# ESP32-USBC.net
KiCad netlist of a schematic drawn in Altium Designer
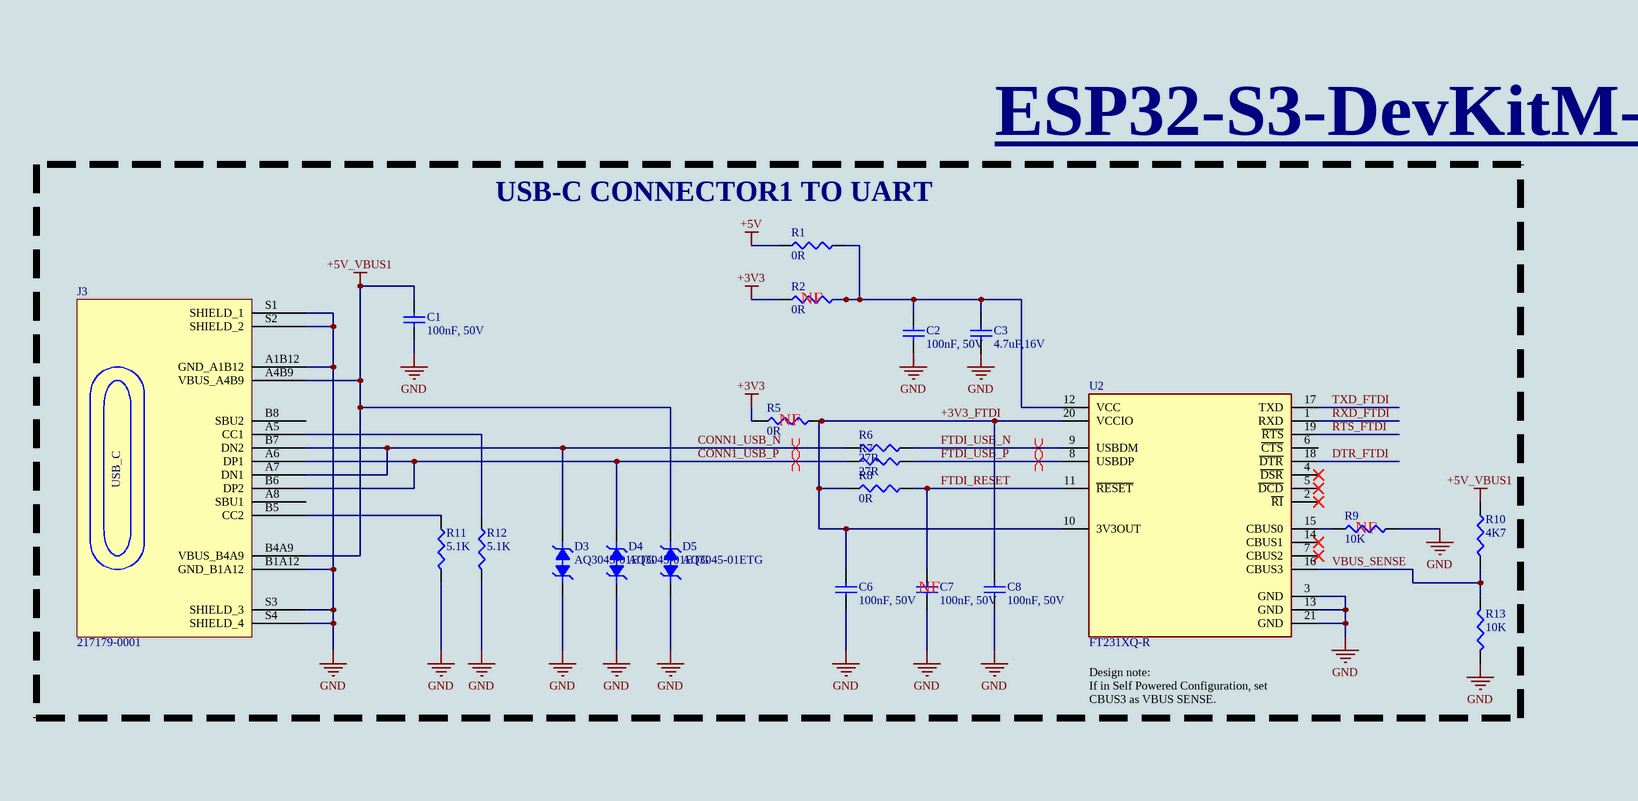
[diagram p0: ESP32-USBC.SchDoc, top left]
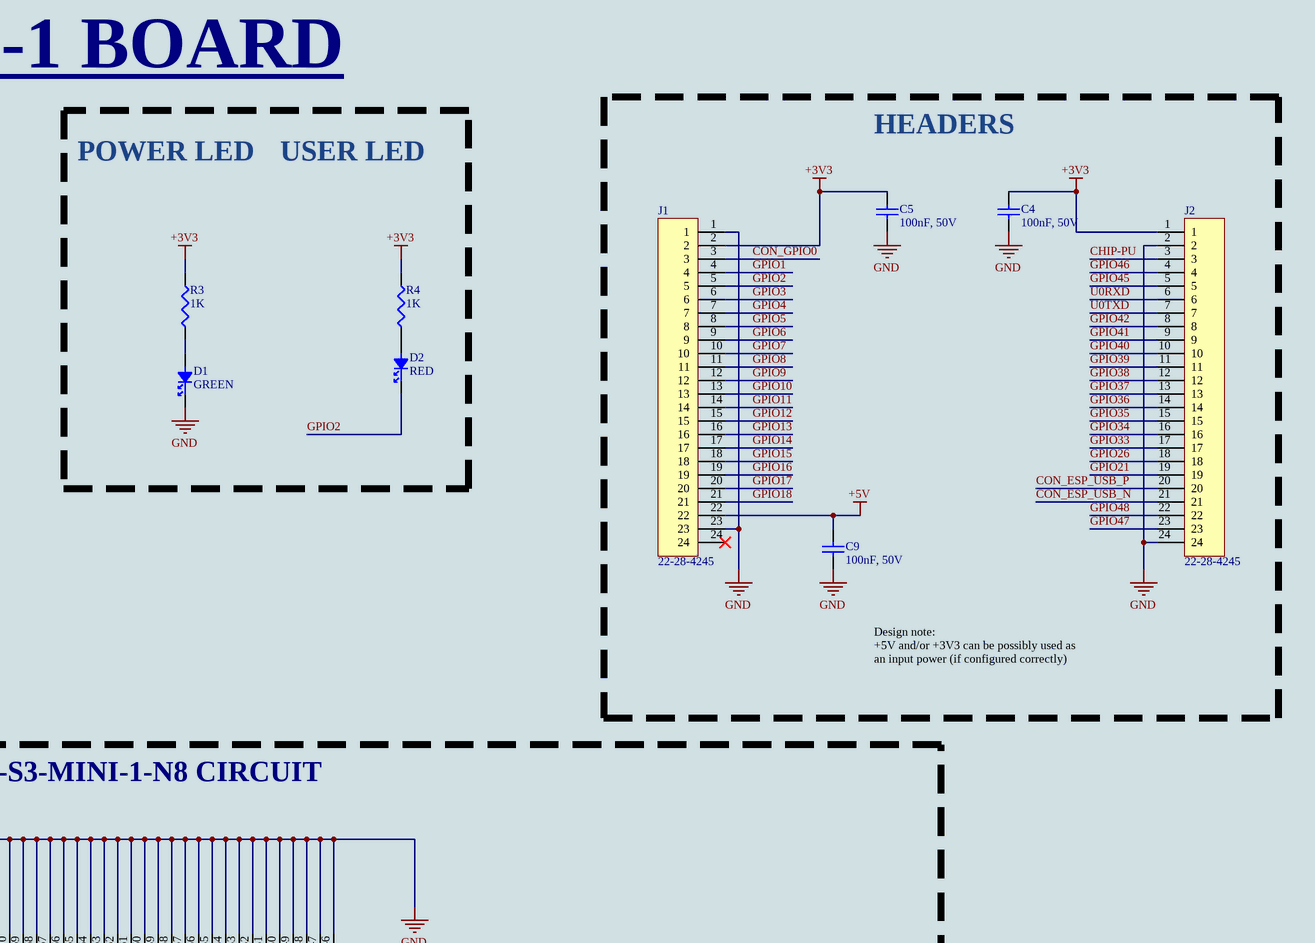
[diagram p1: ESP32-USBC.SchDoc, top right]
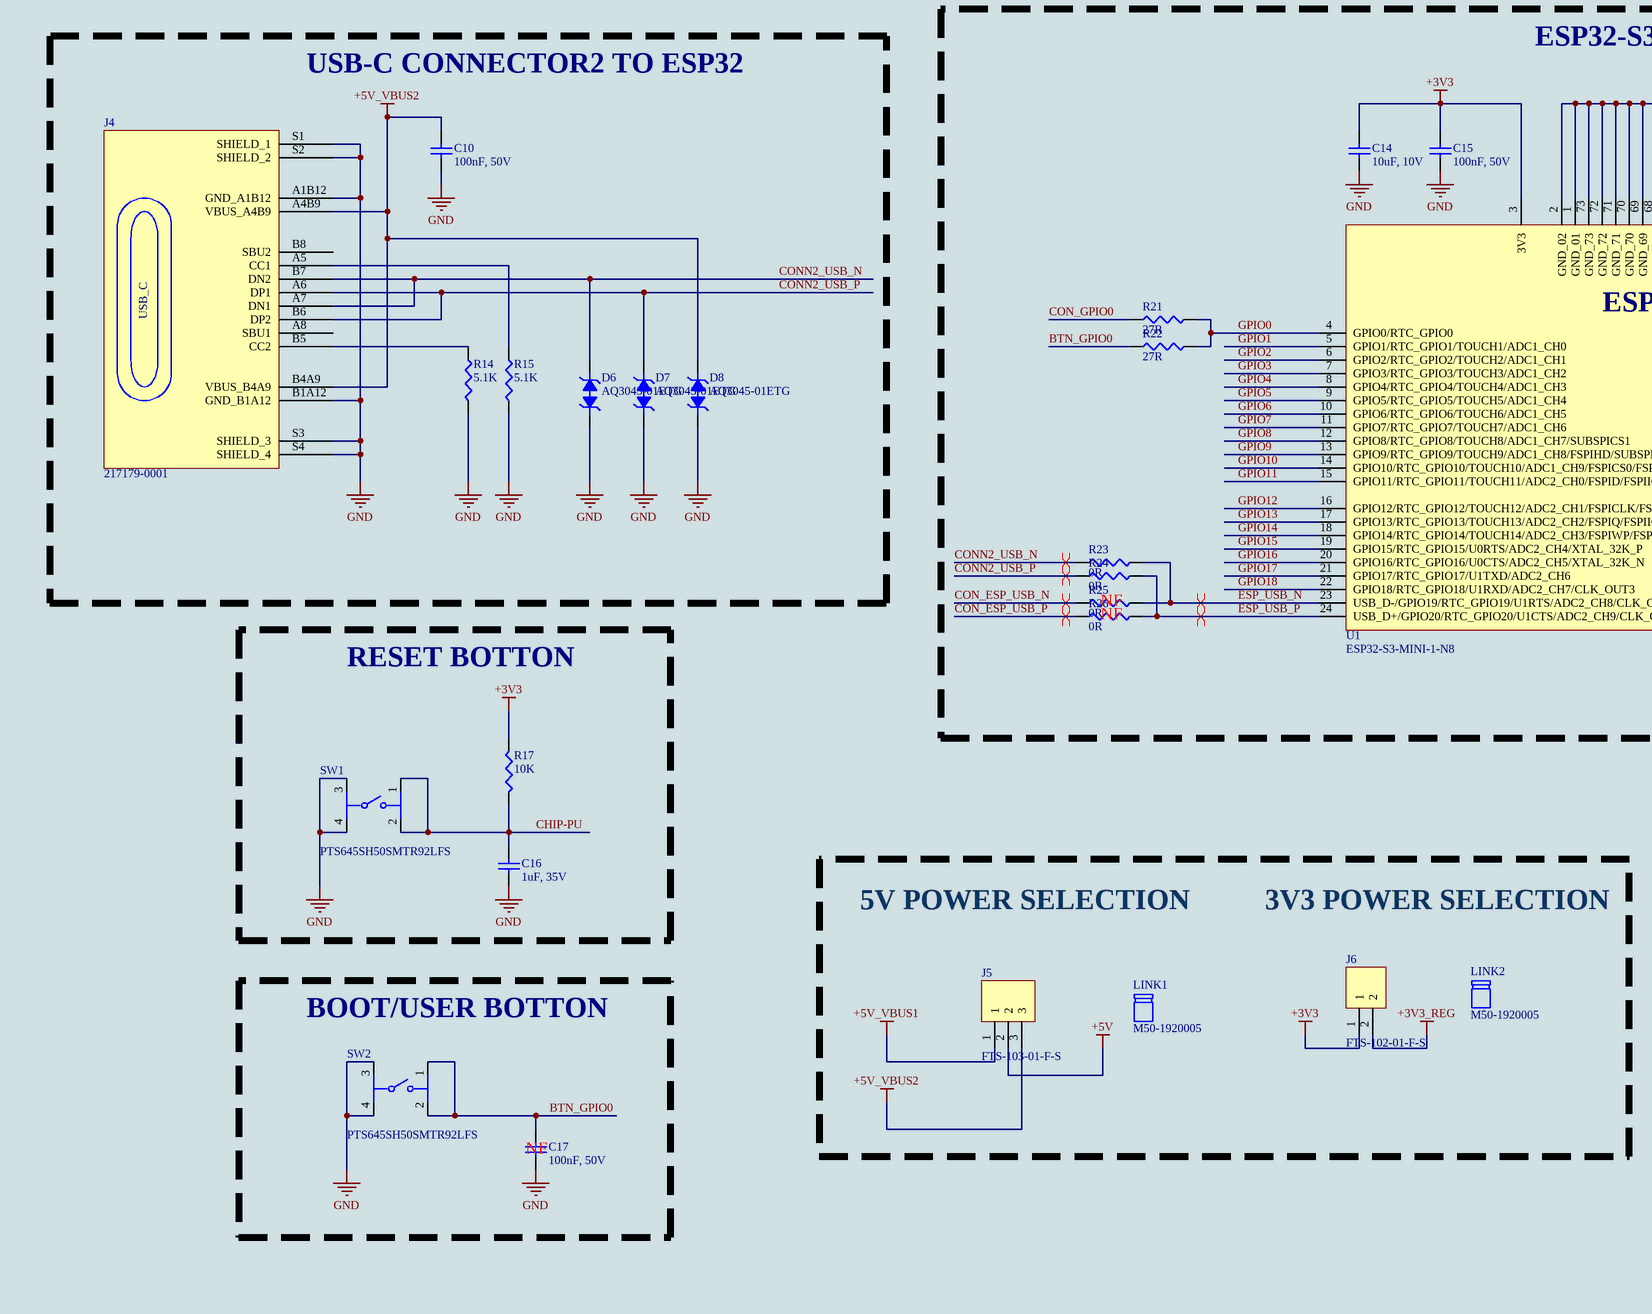
[diagram p2: ESP32-USBC.SchDoc, bottom left]
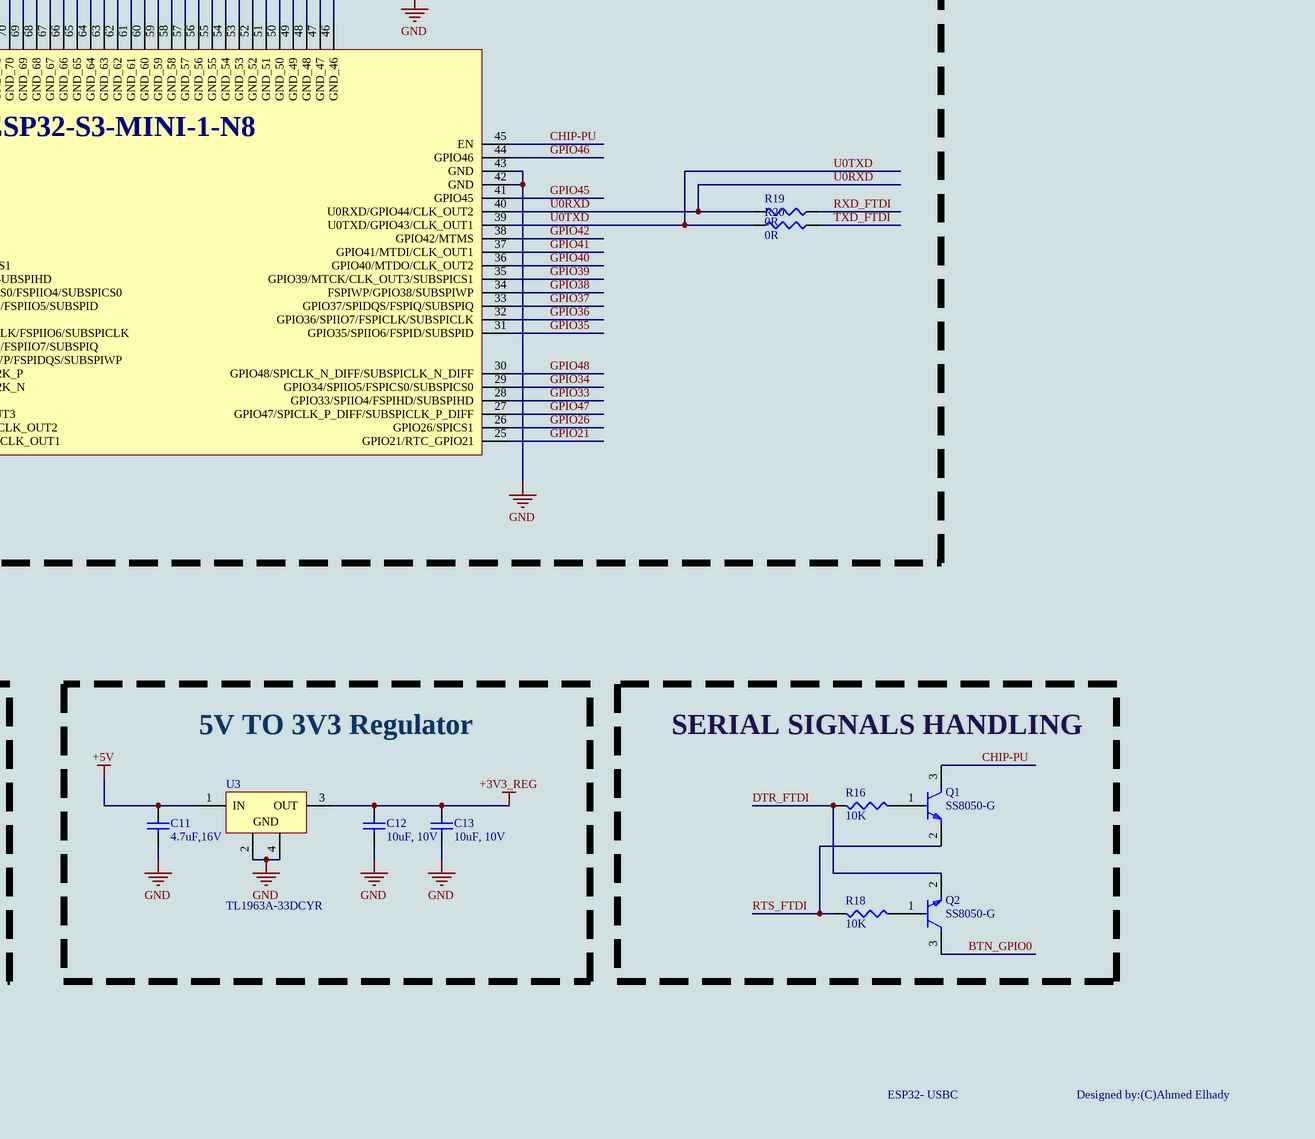
[diagram p3: ESP32-USBC.SchDoc, bottom right]

(export (version "E")
  (design (tool "Eeschema 10.0.6"))
  (components
    (comp (ref "C1")
      (value "100nF, 50V")
      (footprint "CAPC1005X90N")
      (description "50V 100nF X7R ±10% 0402 Multilayer Ceramic Capacitors MLCC - SMD/SMT ROHS")
      (fields
        (field (name "MANUFACTURER") "Samsung Electro-Mechanics")
        (field (name "MANUFACTURER PART NUMBER") "CL05B104KB54PNC")
      )
      (libsource (lib "Schlib") (part "CL05B104KB54PNC"))
    )
    (comp (ref "C2")
      (value "100nF, 50V")
      (footprint "CAPC1005X90N")
      (description "50V 100nF X7R ±10% 0402 Multilayer Ceramic Capacitors MLCC - SMD/SMT ROHS")
      (fields
        (field (name "MANUFACTURER") "Samsung Electro-Mechanics")
        (field (name "MANUFACTURER PART NUMBER") "CL05B104KB54PNC")
      )
      (libsource (lib "Schlib") (part "CL05B104KB54PNC"))
    )
    (comp (ref "C3")
      (value "4.7uF,16V")
      (footprint "CAPC1005X90N")
      (description "4.7 µF ±20% 16V Ceramic Capacitor X5R 0402 (1005 Metric)")
      (fields
        (field (name "MANUFACTURER") "Samsung Electro-Mechanics")
        (field (name "MANUFACTURER PART NUMBER") "CL05A475MO5NUNC")
      )
      (libsource (lib "Schlib") (part "CL05A475MO5NUNC"))
    )
    (comp (ref "C4")
      (value "100nF, 50V")
      (footprint "CAPC1005X90N")
      (description "50V 100nF X7R ±10% 0402 Multilayer Ceramic Capacitors MLCC - SMD/SMT ROHS")
      (fields
        (field (name "MANUFACTURER") "Samsung Electro-Mechanics")
        (field (name "MANUFACTURER PART NUMBER") "CL05B104KB54PNC")
      )
      (libsource (lib "Schlib") (part "CL05B104KB54PNC"))
    )
    (comp (ref "C5")
      (value "100nF, 50V")
      (footprint "CAPC1005X90N")
      (description "50V 100nF X7R ±10% 0402 Multilayer Ceramic Capacitors MLCC - SMD/SMT ROHS")
      (fields
        (field (name "MANUFACTURER") "Samsung Electro-Mechanics")
        (field (name "MANUFACTURER PART NUMBER") "CL05B104KB54PNC")
      )
      (libsource (lib "Schlib") (part "CL05B104KB54PNC"))
    )
    (comp (ref "C6")
      (value "100nF, 50V")
      (footprint "CAPC1005X90N")
      (description "50V 100nF X7R ±10% 0402 Multilayer Ceramic Capacitors MLCC - SMD/SMT ROHS")
      (fields
        (field (name "MANUFACTURER") "Samsung Electro-Mechanics")
        (field (name "MANUFACTURER PART NUMBER") "CL05B104KB54PNC")
      )
      (libsource (lib "Schlib") (part "CL05B104KB54PNC"))
    )
    (comp (ref "C7")
      (value "100nF, 50V")
      (footprint "CAPC1005X90N")
      (description "50V 100nF X7R ±10% 0402 Multilayer Ceramic Capacitors MLCC - SMD/SMT ROHS")
      (fields
        (field (name "MANUFACTURER") "Samsung Electro-Mechanics")
        (field (name "MANUFACTURER PART NUMBER") "CL05B104KB54PNC")
      )
      (libsource (lib "Schlib") (part "CL05B104KB54PNC"))
    )
    (comp (ref "C8")
      (value "100nF, 50V")
      (footprint "CAPC1005X90N")
      (description "50V 100nF X7R ±10% 0402 Multilayer Ceramic Capacitors MLCC - SMD/SMT ROHS")
      (fields
        (field (name "MANUFACTURER") "Samsung Electro-Mechanics")
        (field (name "MANUFACTURER PART NUMBER") "CL05B104KB54PNC")
      )
      (libsource (lib "Schlib") (part "CL05B104KB54PNC"))
    )
    (comp (ref "C9")
      (value "100nF, 50V")
      (footprint "CAPC1005X90N")
      (description "50V 100nF X7R ±10% 0402 Multilayer Ceramic Capacitors MLCC - SMD/SMT ROHS")
      (fields
        (field (name "MANUFACTURER") "Samsung Electro-Mechanics")
        (field (name "MANUFACTURER PART NUMBER") "CL05B104KB54PNC")
      )
      (libsource (lib "Schlib") (part "CL05B104KB54PNC"))
    )
    (comp (ref "C10")
      (value "100nF, 50V")
      (footprint "CAPC1005X90N")
      (description "50V 100nF X7R ±10% 0402 Multilayer Ceramic Capacitors MLCC - SMD/SMT ROHS")
      (fields
        (field (name "MANUFACTURER") "Samsung Electro-Mechanics")
        (field (name "MANUFACTURER PART NUMBER") "CL05B104KB54PNC")
      )
      (libsource (lib "Schlib") (part "CL05B104KB54PNC"))
    )
    (comp (ref "C11")
      (value "4.7uF,16V")
      (footprint "CAPC1005X90N")
      (description "4.7 µF ±20% 16V Ceramic Capacitor X5R 0402 (1005 Metric)")
      (fields
        (field (name "MANUFACTURER") "Samsung Electro-Mechanics")
        (field (name "MANUFACTURER PART NUMBER") "CL05A475MO5NUNC")
      )
      (libsource (lib "Schlib") (part "CL05A475MO5NUNC"))
    )
    (comp (ref "C12")
      (value "10uF, 10V")
      (footprint "CAPC1005X90N")
      (description "10 µF ±20% 10V Ceramic Capacitor X5R 0402 (1005 Metric)")
      (fields
        (field (name "MANUFACTURER") "Samsung Electro-Mechanics")
        (field (name "MANUFACTURER PART NUMBER") "CL05A106MP8NUB8")
      )
      (libsource (lib "Schlib") (part "CL05A106MP8NUB8"))
    )
    (comp (ref "C13")
      (value "10uF, 10V")
      (footprint "CAPC1005X90N")
      (description "10 µF ±20% 10V Ceramic Capacitor X5R 0402 (1005 Metric)")
      (fields
        (field (name "MANUFACTURER") "Samsung Electro-Mechanics")
        (field (name "MANUFACTURER PART NUMBER") "CL05A106MP8NUB8")
      )
      (libsource (lib "Schlib") (part "CL05A106MP8NUB8"))
    )
    (comp (ref "C14")
      (value "10uF, 10V")
      (footprint "CAPC1005X90N")
      (description "10 µF ±20% 10V Ceramic Capacitor X5R 0402 (1005 Metric)")
      (fields
        (field (name "MANUFACTURER") "Samsung Electro-Mechanics")
        (field (name "MANUFACTURER PART NUMBER") "CL05A106MP8NUB8")
      )
      (libsource (lib "Schlib") (part "CL05A106MP8NUB8"))
    )
    (comp (ref "C15")
      (value "100nF, 50V")
      (footprint "CAPC1005X90N")
      (description "50V 100nF X7R ±10% 0402 Multilayer Ceramic Capacitors MLCC - SMD/SMT ROHS")
      (fields
        (field (name "MANUFACTURER") "Samsung Electro-Mechanics")
        (field (name "MANUFACTURER PART NUMBER") "CL05B104KB54PNC")
      )
      (libsource (lib "Schlib") (part "CL05B104KB54PNC"))
    )
    (comp (ref "C16")
      (value "1uF, 35V")
      (footprint "CAPC1005X90N")
      (description "1 µF ±10% 35V Ceramic Capacitor X5R 0402 (1005 Metric)")
      (fields
        (field (name "MANUFACTURER") "Samsung Electro-Mechanics")
        (field (name "MANUFACTURER PART NUMBER") "CL05A105KL5NRNC")
      )
      (libsource (lib "Schlib") (part "CL05A105KL5NRNC"))
    )
    (comp (ref "C17")
      (value "100nF, 50V")
      (footprint "CAPC1005X90N")
      (description "50V 100nF X7R ±10% 0402 Multilayer Ceramic Capacitors MLCC - SMD/SMT ROHS")
      (fields
        (field (name "MANUFACTURER") "Samsung Electro-Mechanics")
        (field (name "MANUFACTURER PART NUMBER") "CL05B104KB54PNC")
      )
      (libsource (lib "Schlib") (part "CL05B104KB54PNC"))
    )
    (comp (ref "D1")
      (value "GREEN")
      (footprint "LED0402G")
      (description "Yellow-Green 571nm LED Indication - Discrete 2V 0402 (1005 Metric)")
      (fields
        (field (name "MANUFACTURER") "Vishay")
        (field (name "MANUFACTURER PART NUMBER") "VLMG1500-GS08")
      )
      (libsource (lib "Schlib") (part "VLMG1500-GS08"))
    )
    (comp (ref "D2")
      (value "RED")
      (footprint "LED0402R")
      (description "Red 631nm LED Indication - Discrete 2V 0402 (1005 Metric)")
      (fields
        (field (name "MANUFACTURER") "Vishay")
        (field (name "MANUFACTURER PART NUMBER") "VLMS1500-GS08")
      )
      (libsource (lib "Schlib") (part "VLMS1500-GS08"))
    )
    (comp (ref "D3")
      (value "AQ3045-01ETG")
      (footprint "SOD882")
      (description "12V Clamp 3A (8/20µs) Ipp Tvs Diode Surface Mount SOD-882")
      (fields (field (name "MANUFACTURER") "Littelfuse"))
      (libsource (lib "Schlib") (part "AQ3045-01ETG"))
    )
    (comp (ref "D4")
      (value "AQ3045-01ETG")
      (footprint "SOD882")
      (description "12V Clamp 3A (8/20µs) Ipp Tvs Diode Surface Mount SOD-882")
      (fields (field (name "MANUFACTURER") "Littelfuse"))
      (libsource (lib "Schlib") (part "AQ3045-01ETG"))
    )
    (comp (ref "D5")
      (value "AQ3045-01ETG")
      (footprint "SOD882")
      (description "12V Clamp 3A (8/20µs) Ipp Tvs Diode Surface Mount SOD-882")
      (fields (field (name "MANUFACTURER") "Littelfuse"))
      (libsource (lib "Schlib") (part "AQ3045-01ETG"))
    )
    (comp (ref "D6")
      (value "AQ3045-01ETG")
      (footprint "SOD882")
      (description "12V Clamp 3A (8/20µs) Ipp Tvs Diode Surface Mount SOD-882")
      (fields (field (name "MANUFACTURER") "Littelfuse"))
      (libsource (lib "Schlib") (part "AQ3045-01ETG"))
    )
    (comp (ref "D7")
      (value "AQ3045-01ETG")
      (footprint "SOD882")
      (description "12V Clamp 3A (8/20µs) Ipp Tvs Diode Surface Mount SOD-882")
      (fields (field (name "MANUFACTURER") "Littelfuse"))
      (libsource (lib "Schlib") (part "AQ3045-01ETG"))
    )
    (comp (ref "D8")
      (value "AQ3045-01ETG")
      (footprint "SOD882")
      (description "12V Clamp 3A (8/20µs) Ipp Tvs Diode Surface Mount SOD-882")
      (fields (field (name "MANUFACTURER") "Littelfuse"))
      (libsource (lib "Schlib") (part "AQ3045-01ETG"))
    )
    (comp (ref "J1")
      (value "22-28-4245")
      (footprint "HDR1x24_2.54MM")
      (description "24 Connector Header Through Hole 24 position 0.100\" (2.54mm)")
      (fields (field (name "MANUFACTURER") "Molex") (field (name "LCSC PART NUMBER") "C7145888"))
      (libsource (lib "Schlib") (part "22-28-4245"))
    )
    (comp (ref "J2")
      (value "22-28-4245")
      (footprint "HDR1x24_2.54MM")
      (description "24 Connector Header Through Hole 24 position 0.100\" (2.54mm)")
      (fields (field (name "MANUFACTURER") "Molex") (field (name "LCSC PART NUMBER") "C7145888"))
      (libsource (lib "") (part "22-28-4245_1"))
    )
    (comp (ref "J3")
      (value "217179-0001")
      (footprint "FP-2171790001-MFG - duplicate")
      (fields (field (name "MANUFACTURER") "Molex") (field (name "LCSC PART NUMBER") "2171790001"))
      (libsource (lib "Schlib") (part "217179-0001"))
    )
    (comp (ref "J4")
      (value "217179-0001")
      (footprint "FP-2171790001-MFG - duplicate")
      (fields (field (name "MANUFACTURER") "Molex") (field (name "LCSC PART NUMBER") "2171790001"))
      (libsource (lib "Schlib") (part "217179-0001"))
    )
    (comp (ref "J5")
      (value "FTS-103-01-F-S")
      (footprint "HDR1X3_1.27MM")
      (description "Connector Header Through Hole 3 position 0.050\" (1.27mm)")
      (fields (field (name "MANUFACTURER") "Samtec") (field (name "LCSC PART NUMBER") "C3333578"))
      (libsource (lib "Schlib") (part "FTS-103-01-F-S"))
    )
    (comp (ref "J6")
      (value "FTS-102-01-F-S")
      (footprint "HDR1X2_1.27MM")
      (description "Connector Header Through Hole 2 position 0.050\" (1.27mm)")
      (fields (field (name "MANUFACTURER") "Samtec") (field (name "LCSC PART NUMBER") "C6045317"))
      (libsource (lib "Schlib") (part "FTS-102-01-F-S"))
    )
    (comp (ref "LINK1")
      (value "M50-1920005")
      (description "1.27mm (0.05) Pitch Closed Top Jumper Socket, red, gold\"")
      (fields (field (name "MANUFACTURER") "Harwin") (field (name "LCSC PART NUMBER") "C6985646"))
      (libsource (lib "Schlib") (part "M50-1920005"))
    )
    (comp (ref "LINK2")
      (value "M50-1920005")
      (description "1.27mm (0.05) Pitch Closed Top Jumper Socket, red, gold\"")
      (fields (field (name "MANUFACTURER") "Harwin") (field (name "LCSC PART NUMBER") "C6985646"))
      (libsource (lib "Schlib") (part "M50-1920005"))
    )
    (comp (ref "Q1")
      (value "SS8050-G")
      (footprint "FP-SS8050-G-IPC_B")
      (description "Bipolar (BJT) Transistor NPN 25 V 1.5 A 100MHz 300 mW Surface Mount SOT-23-3")
      (fields (field (name "MANUFACTURER") "Comchip") (field (name "LCSC PART NUMBER") "C3199946"))
      (libsource (lib "Schlib") (part "SS8050-G"))
    )
    (comp (ref "Q2")
      (value "SS8050-G")
      (footprint "FP-SS8050-G-IPC_B")
      (description "Bipolar (BJT) Transistor NPN 25 V 1.5 A 100MHz 300 mW Surface Mount SOT-23-3")
      (fields (field (name "MANUFACTURER") "Comchip") (field (name "LCSC PART NUMBER") "C3199946"))
      (libsource (lib "Schlib") (part "SS8050-G"))
    )
    (comp (ref "R1")
      (value "0R")
      (footprint "RESC1005X37N")
      (description "0 Ohms Jumper Chip Resistor 0402 (1005 Metric) Moisture Resistant Thick Film")
      (fields
        (field (name "MANUFACTURER") "Yageo Group")
        (field (name "MANUFACTURER PART NUMBER") "RC0402JR-070RL")
      )
      (libsource (lib "Schlib") (part "RC0402JR-070RL"))
    )
    (comp (ref "R2")
      (value "0R")
      (footprint "RESC1005X37N")
      (description "0 Ohms Jumper Chip Resistor 0402 (1005 Metric) Moisture Resistant Thick Film")
      (fields
        (field (name "MANUFACTURER") "Yageo Group")
        (field (name "MANUFACTURER PART NUMBER") "RC0402JR-070RL")
      )
      (libsource (lib "Schlib") (part "RC0402JR-070RL"))
    )
    (comp (ref "R3")
      (value "1K")
      (footprint "RESC1005X37N")
      (description "1 kOhms ±1% 0.063W, 1/16W Chip Resistor 0402 (1005 Metric) Moisture Resistant Thick Film")
      (fields
        (field (name "MANUFACTURER") "Yageo Group")
        (field (name "MANUFACTURER PART NUMBER") "RC0402FR-071KL")
      )
      (libsource (lib "Schlib") (part "RC0402FR-071KL"))
    )
    (comp (ref "R4")
      (value "1K")
      (footprint "RESC1005X37N")
      (description "1 kOhms ±1% 0.063W, 1/16W Chip Resistor 0402 (1005 Metric) Moisture Resistant Thick Film")
      (fields
        (field (name "MANUFACTURER") "Yageo Group")
        (field (name "MANUFACTURER PART NUMBER") "RC0402FR-071KL")
      )
      (libsource (lib "Schlib") (part "RC0402FR-071KL"))
    )
    (comp (ref "R5")
      (value "0R")
      (footprint "RESC1005X37N")
      (description "0 Ohms Jumper Chip Resistor 0402 (1005 Metric) Moisture Resistant Thick Film")
      (fields
        (field (name "MANUFACTURER") "Yageo Group")
        (field (name "MANUFACTURER PART NUMBER") "RC0402JR-070RL")
      )
      (libsource (lib "Schlib") (part "RC0402JR-070RL"))
    )
    (comp (ref "R6")
      (value "27R")
      (footprint "RESC1005X37N")
      (description "27 Ohms ±1% 0.063W, 1/16W Chip Resistor 0402 (1005 Metric) Moisture Resistant Thick Film")
      (fields
        (field (name "MANUFACTURER") "Yageo Group")
        (field (name "MANUFACTURER PART NUMBER") "RC0402FR-0727RL")
      )
      (libsource (lib "Schlib") (part "RC0402FR-0727RL"))
    )
    (comp (ref "R7")
      (value "27R")
      (footprint "RESC1005X37N")
      (description "27 Ohms ±1% 0.063W, 1/16W Chip Resistor 0402 (1005 Metric) Moisture Resistant Thick Film")
      (fields
        (field (name "MANUFACTURER") "Yageo Group")
        (field (name "MANUFACTURER PART NUMBER") "RC0402FR-0727RL")
      )
      (libsource (lib "Schlib") (part "RC0402FR-0727RL"))
    )
    (comp (ref "R8")
      (value "0R")
      (footprint "RESC1005X37N")
      (description "0 Ohms Jumper Chip Resistor 0402 (1005 Metric) Moisture Resistant Thick Film")
      (fields
        (field (name "MANUFACTURER") "Yageo Group")
        (field (name "MANUFACTURER PART NUMBER") "RC0402JR-070RL")
      )
      (libsource (lib "Schlib") (part "RC0402JR-070RL"))
    )
    (comp (ref "R9")
      (value "10K")
      (footprint "RESC1005X37N")
      (fields
        (field (name "MANUFACTURER") "Yageo Group")
        (field (name "MANUFACTURER PART NUMBER") "AC0402FR-0710KL")
        (field (name "TOLERANCE") "1%")
      )
      (libsource (lib "Schlib") (part "AC0402FR-0710KL"))
    )
    (comp (ref "R10")
      (value "4K7")
      (footprint "RESC1005X37N")
      (description "4.7 kOhms ±1% 0.063W, 1/16W Chip Resistor 0402 (1005 Metric) Moisture Resistant Thick Film")
      (fields
        (field (name "MANUFACTURER") "Yageo Group")
        (field (name "MANUFACTURER PART NUMBER") "RC0402FR-074K7L")
      )
      (libsource (lib "Schlib") (part "RC0402FR-074K7L"))
    )
    (comp (ref "R11")
      (value "5.1K")
      (footprint "RESC1005X37N")
      (fields
        (field (name "MANUFACTURER") "Yageo Group")
        (field (name "MANUFACTURER PART NUMBER") "AC0402FR-075K1L")
        (field (name "TOLERANCE") "1%")
      )
      (libsource (lib "Schlib") (part "AC0402FR-075K1L"))
    )
    (comp (ref "R12")
      (value "5.1K")
      (footprint "RESC1005X37N")
      (fields
        (field (name "MANUFACTURER") "Yageo Group")
        (field (name "MANUFACTURER PART NUMBER") "AC0402FR-075K1L")
        (field (name "TOLERANCE") "1%")
      )
      (libsource (lib "Schlib") (part "AC0402FR-075K1L"))
    )
    (comp (ref "R13")
      (value "10K")
      (footprint "RESC1005X37N")
      (fields
        (field (name "MANUFACTURER") "Yageo Group")
        (field (name "MANUFACTURER PART NUMBER") "AC0402FR-0710KL")
        (field (name "TOLERANCE") "1%")
      )
      (libsource (lib "Schlib") (part "AC0402FR-0710KL"))
    )
    (comp (ref "R14")
      (value "5.1K")
      (footprint "RESC1005X37N")
      (fields
        (field (name "MANUFACTURER") "Yageo Group")
        (field (name "MANUFACTURER PART NUMBER") "AC0402FR-075K1L")
        (field (name "TOLERANCE") "1%")
      )
      (libsource (lib "Schlib") (part "AC0402FR-075K1L"))
    )
    (comp (ref "R15")
      (value "5.1K")
      (footprint "RESC1005X37N")
      (fields
        (field (name "MANUFACTURER") "Yageo Group")
        (field (name "MANUFACTURER PART NUMBER") "AC0402FR-075K1L")
        (field (name "TOLERANCE") "1%")
      )
      (libsource (lib "Schlib") (part "AC0402FR-075K1L"))
    )
    (comp (ref "R16")
      (value "10K")
      (footprint "RESC1005X37N")
      (fields
        (field (name "MANUFACTURER") "Yageo Group")
        (field (name "MANUFACTURER PART NUMBER") "AC0402FR-0710KL")
        (field (name "TOLERANCE") "1%")
      )
      (libsource (lib "Schlib") (part "AC0402FR-0710KL"))
    )
    (comp (ref "R17")
      (value "10K")
      (footprint "RESC1005X37N")
      (fields
        (field (name "MANUFACTURER") "Yageo Group")
        (field (name "MANUFACTURER PART NUMBER") "AC0402FR-0710KL")
        (field (name "TOLERANCE") "1%")
      )
      (libsource (lib "Schlib") (part "AC0402FR-0710KL"))
    )
    (comp (ref "R18")
      (value "10K")
      (footprint "RESC1005X37N")
      (fields
        (field (name "MANUFACTURER") "Yageo Group")
        (field (name "MANUFACTURER PART NUMBER") "AC0402FR-0710KL")
        (field (name "TOLERANCE") "1%")
      )
      (libsource (lib "Schlib") (part "AC0402FR-0710KL"))
    )
    (comp (ref "R19")
      (value "0R")
      (footprint "RESC1005X37N")
      (description "0 Ohms Jumper Chip Resistor 0402 (1005 Metric) Moisture Resistant Thick Film")
      (fields
        (field (name "MANUFACTURER") "Yageo Group")
        (field (name "MANUFACTURER PART NUMBER") "RC0402JR-070RL")
      )
      (libsource (lib "Schlib") (part "RC0402JR-070RL"))
    )
    (comp (ref "R20")
      (value "0R")
      (footprint "RESC1005X37N")
      (description "0 Ohms Jumper Chip Resistor 0402 (1005 Metric) Moisture Resistant Thick Film")
      (fields
        (field (name "MANUFACTURER") "Yageo Group")
        (field (name "MANUFACTURER PART NUMBER") "RC0402JR-070RL")
      )
      (libsource (lib "Schlib") (part "RC0402JR-070RL"))
    )
    (comp (ref "R21")
      (value "27R")
      (footprint "RESC1005X37N")
      (description "27 Ohms ±1% 0.063W, 1/16W Chip Resistor 0402 (1005 Metric) Moisture Resistant Thick Film")
      (fields
        (field (name "MANUFACTURER") "Yageo Group")
        (field (name "MANUFACTURER PART NUMBER") "RC0402FR-0727RL")
      )
      (libsource (lib "Schlib") (part "RC0402FR-0727RL"))
    )
    (comp (ref "R22")
      (value "27R")
      (footprint "RESC1005X37N")
      (description "27 Ohms ±1% 0.063W, 1/16W Chip Resistor 0402 (1005 Metric) Moisture Resistant Thick Film")
      (fields
        (field (name "MANUFACTURER") "Yageo Group")
        (field (name "MANUFACTURER PART NUMBER") "RC0402FR-0727RL")
      )
      (libsource (lib "Schlib") (part "RC0402FR-0727RL"))
    )
    (comp (ref "R23")
      (value "0R")
      (footprint "RESC1005X37N")
      (description "0 Ohms Jumper Chip Resistor 0402 (1005 Metric) Moisture Resistant Thick Film")
      (fields
        (field (name "MANUFACTURER") "Yageo Group")
        (field (name "MANUFACTURER PART NUMBER") "RC0402JR-070RL")
      )
      (libsource (lib "Schlib") (part "RC0402JR-070RL"))
    )
    (comp (ref "R24")
      (value "0R")
      (footprint "RESC1005X37N")
      (description "0 Ohms Jumper Chip Resistor 0402 (1005 Metric) Moisture Resistant Thick Film")
      (fields
        (field (name "MANUFACTURER") "Yageo Group")
        (field (name "MANUFACTURER PART NUMBER") "RC0402JR-070RL")
      )
      (libsource (lib "Schlib") (part "RC0402JR-070RL"))
    )
    (comp (ref "R25")
      (value "0R")
      (footprint "RESC1005X37N")
      (description "0 Ohms Jumper Chip Resistor 0402 (1005 Metric) Moisture Resistant Thick Film")
      (fields
        (field (name "MANUFACTURER") "Yageo Group")
        (field (name "MANUFACTURER PART NUMBER") "RC0402JR-070RL")
      )
      (libsource (lib "Schlib") (part "RC0402JR-070RL"))
    )
    (comp (ref "R26")
      (value "0R")
      (footprint "RESC1005X37N")
      (description "0 Ohms Jumper Chip Resistor 0402 (1005 Metric) Moisture Resistant Thick Film")
      (fields
        (field (name "MANUFACTURER") "Yageo Group")
        (field (name "MANUFACTURER PART NUMBER") "RC0402JR-070RL")
      )
      (libsource (lib "Schlib") (part "RC0402JR-070RL"))
    )
    (comp (ref "SW1")
      (value "PTS645SH50SMTR92LFS")
      (footprint "FP-PTS645SH50SMTR92LFS-MFG")
      (description "Tactile Switch SPST-NO Top Actuated Surface Mount")
      (fields (field (name "MANUFACTURER") "C&K Components"))
      (libsource (lib "Schlib") (part "PTS645SH50SMTR92LFS"))
    )
    (comp (ref "SW2")
      (value "PTS645SH50SMTR92LFS")
      (footprint "FP-PTS645SH50SMTR92LFS-MFG")
      (description "Tactile Switch SPST-NO Top Actuated Surface Mount")
      (fields (field (name "MANUFACTURER") "C&K Components"))
      (libsource (lib "Schlib") (part "PTS645SH50SMTR92LFS"))
    )
    (comp (ref "U1")
      (value "ESP32-S3-MINI-1-N8")
      (footprint "XCVR_ESP32-S3-MINI-1-N8")
      (description "20.5dBm ESP32-S3FN8 Chip 2.4GHz SMD WiFi Modules ROHS")
      (fields (field (name "MANUFACTURER") "Espressif Systems") (field (name "LCSC PART NUMBER") "C2913206"))
      (libsource (lib "Schlib") (part "ESP32-S3-MINI-1-N8"))
    )
    (comp (ref "U2")
      (value "FT231XQ-R")
      (footprint "FP-QFN-20-IPC_B")
      (description "USB Bridge, USB to UART USB 2.0 UART Interface 20-QFN (4x4)")
      (fields (field (name "MANUFACTURER") "FTDI") (field (name "LCSC PART NUMBER") "C132159"))
      (libsource (lib "Schlib") (part "FT231XQ-R"))
    )
    (comp (ref "U3")
      (value "TL1963A-33DCYR")
      (footprint "FP-SS8050-G-IPC_B")
      (description "Linear Voltage Regulator IC Positive Fixed 1 Output 1.5A SOT-223-4")
      (fields (field (name "MANUFACTURER") "Texas Instruments") (field (name "LCSC PART NUMBER") "C181262"))
      (libsource (lib "Schlib") (part "TL1963A-33DCYR"))
    )
  )
  (nets
    (net (code "1") (name "+3V3") (class "Default")
      (node (ref "C14") (pin "2") (pinfunction "2_2") (pintype "passive"))
      (node (ref "C15") (pin "2") (pinfunction "2_2") (pintype "passive"))
      (node (ref "C4") (pin "2") (pinfunction "2_2") (pintype "passive"))
      (node (ref "C5") (pin "2") (pinfunction "2_2") (pintype "passive"))
      (node (ref "J1") (pin "2") (pinfunction "2_2") (pintype "passive"))
      (node (ref "J2") (pin "1") (pinfunction "1_1") (pintype "passive"))
      (node (ref "J6") (pin "1") (pinfunction "1_1") (pintype "passive"))
      (node (ref "R17") (pin "11") (pinfunction "6_11") (pintype "passive"))
      (node (ref "R2") (pin "1") (pinfunction "1_1") (pintype "passive"))
      (node (ref "R3") (pin "11") (pinfunction "6_11") (pintype "passive"))
      (node (ref "R4") (pin "11") (pinfunction "6_11") (pintype "passive"))
      (node (ref "R5") (pin "1") (pinfunction "1_1") (pintype "passive"))
      (node (ref "U1") (pin "3") (pinfunction "3V3_3") (pintype "power_in"))
    )
    (net (code "2") (name "+3V3_REG") (class "Default")
      (node (ref "C12") (pin "2") (pinfunction "2_2") (pintype "passive"))
      (node (ref "C13") (pin "2") (pinfunction "2_2") (pintype "passive"))
      (node (ref "J6") (pin "2") (pinfunction "2_2") (pintype "passive"))
      (node (ref "U3") (pin "3") (pinfunction "OUT_3") (pintype "power_in"))
    )
    (net (code "3") (name "+5V") (class "Default")
      (node (ref "C11") (pin "2") (pinfunction "2_2") (pintype "passive"))
      (node (ref "C9") (pin "2") (pinfunction "2_2") (pintype "passive"))
      (node (ref "J1") (pin "22") (pinfunction "22_22") (pintype "passive"))
      (node (ref "J5") (pin "2") (pinfunction "2_2") (pintype "passive"))
      (node (ref "R1") (pin "1") (pinfunction "1_1") (pintype "passive"))
      (node (ref "U3") (pin "1") (pinfunction "IN_1") (pintype "power_in"))
    )
    (net (code "4") (name "+5V_VBUS1") (class "Default")
      (node (ref "C1") (pin "2") (pinfunction "2_2") (pintype "passive"))
      (node (ref "D5") (pin "2") (pinfunction "2_2") (pintype "passive"))
      (node (ref "J3") (pin "A4B9") (pinfunction "VBUS_A4B9_A4B9") (pintype "passive"))
      (node (ref "J3") (pin "B4A9") (pinfunction "VBUS_B4A9_B4A9") (pintype "passive"))
      (node (ref "J5") (pin "1") (pinfunction "1_1") (pintype "passive"))
      (node (ref "R10") (pin "2") (pinfunction "2_2") (pintype "passive"))
    )
    (net (code "5") (name "+5V_VBUS2") (class "Default")
      (node (ref "C10") (pin "2") (pinfunction "2_2") (pintype "passive"))
      (node (ref "D8") (pin "2") (pinfunction "2_2") (pintype "passive"))
      (node (ref "J4") (pin "A4B9") (pinfunction "VBUS_A4B9_A4B9") (pintype "passive"))
      (node (ref "J4") (pin "B4A9") (pinfunction "VBUS_B4A9_B4A9") (pintype "passive"))
      (node (ref "J5") (pin "3") (pinfunction "3_3") (pintype "passive"))
    )
    (net (code "6") (name "/+3V3_FTDI") (class "Default")
      (node (ref "C6") (pin "2") (pinfunction "2_2") (pintype "passive"))
      (node (ref "C8") (pin "2") (pinfunction "2_2") (pintype "passive"))
      (node (ref "R5") (pin "2") (pinfunction "2_2") (pintype "passive"))
      (node (ref "R8") (pin "1") (pinfunction "1_1") (pintype "passive"))
      (node (ref "U2") (pin "10") (pinfunction "3V3OUT_10") (pintype "passive"))
      (node (ref "U2") (pin "20") (pinfunction "VCCIO_20") (pintype "power_in"))
    )
    (net (code "7") (name "/BTN_GPIO0") (class "Default")
      (node (ref "C17") (pin "2") (pinfunction "2_2") (pintype "passive"))
      (node (ref "Q2") (pin "3") (pinfunction "C_3") (pintype "passive"))
      (node (ref "R22") (pin "1") (pinfunction "1_1") (pintype "passive"))
      (node (ref "SW2") (pin "1") (pinfunction "1_1") (pintype "passive"))
      (node (ref "SW2") (pin "2") (pinfunction "2_2") (pintype "passive"))
    )
    (net (code "8") (name "/CHIP-PU") (class "Default")
      (node (ref "C16") (pin "2") (pinfunction "2_2") (pintype "passive"))
      (node (ref "J2") (pin "3") (pinfunction "3_3") (pintype "passive"))
      (node (ref "Q1") (pin "3") (pinfunction "C_3") (pintype "passive"))
      (node (ref "R17") (pin "10") (pinfunction "5_10") (pintype "passive"))
      (node (ref "SW1") (pin "1") (pinfunction "1_1") (pintype "passive"))
      (node (ref "SW1") (pin "2") (pinfunction "2_2") (pintype "passive"))
      (node (ref "U1") (pin "45") (pinfunction "EN_45") (pintype "passive"))
    )
    (net (code "9") (name "/CONN1_USB_N") (class "Default")
      (node (ref "D3") (pin "2") (pinfunction "2_2") (pintype "passive"))
      (node (ref "J3") (pin "A7") (pinfunction "DN1_A7") (pintype "passive"))
      (node (ref "J3") (pin "B7") (pinfunction "DN2_B7") (pintype "passive"))
      (node (ref "R6") (pin "1") (pinfunction "1_1") (pintype "passive"))
    )
    (net (code "10") (name "/CONN1_USB_P") (class "Default")
      (node (ref "D4") (pin "2") (pinfunction "2_2") (pintype "passive"))
      (node (ref "J3") (pin "A6") (pinfunction "DP1_A6") (pintype "passive"))
      (node (ref "J3") (pin "B6") (pinfunction "DP2_B6") (pintype "passive"))
      (node (ref "R7") (pin "1") (pinfunction "1_1") (pintype "passive"))
    )
    (net (code "11") (name "/CONN2_USB_N") (class "Default")
      (node (ref "D6") (pin "2") (pinfunction "2_2") (pintype "passive"))
      (node (ref "J4") (pin "A7") (pinfunction "DN1_A7") (pintype "passive"))
      (node (ref "J4") (pin "B7") (pinfunction "DN2_B7") (pintype "passive"))
      (node (ref "R23") (pin "1") (pinfunction "1_1") (pintype "passive"))
    )
    (net (code "12") (name "/CONN2_USB_P") (class "Default")
      (node (ref "D7") (pin "2") (pinfunction "2_2") (pintype "passive"))
      (node (ref "J4") (pin "A6") (pinfunction "DP1_A6") (pintype "passive"))
      (node (ref "J4") (pin "B6") (pinfunction "DP2_B6") (pintype "passive"))
      (node (ref "R24") (pin "1") (pinfunction "1_1") (pintype "passive"))
    )
    (net (code "13") (name "/CON_ESP_USB_N") (class "Default")
      (node (ref "J2") (pin "21") (pinfunction "21_21") (pintype "passive"))
      (node (ref "R25") (pin "1") (pinfunction "1_1") (pintype "passive"))
    )
    (net (code "14") (name "/CON_ESP_USB_P") (class "Default")
      (node (ref "J2") (pin "20") (pinfunction "20_20") (pintype "passive"))
      (node (ref "R26") (pin "1") (pinfunction "1_1") (pintype "passive"))
    )
    (net (code "15") (name "/CON_GPIO0") (class "Default")
      (node (ref "J1") (pin "3") (pinfunction "3_3") (pintype "passive"))
      (node (ref "R21") (pin "1") (pinfunction "1_1") (pintype "passive"))
    )
    (net (code "16") (name "/DTR_FTDI") (class "Default")
      (node (ref "Q2") (pin "2") (pinfunction "E_2") (pintype "passive"))
      (node (ref "R16") (pin "10") (pinfunction "5_10") (pintype "passive"))
      (node (ref "U2") (pin "18") (pinfunction "~{DTR}_18") (pintype "passive"))
    )
    (net (code "17") (name "/ESP_USB_N") (class "Default")
      (node (ref "R23") (pin "2") (pinfunction "2_2") (pintype "passive"))
      (node (ref "R25") (pin "2") (pinfunction "2_2") (pintype "passive"))
      (node (ref "U1") (pin "23") (pinfunction "USB_D-/GPIO19/RTC_GPIO19/U1RTS/ADC2_CH8/CLK_OUT2_23") (pintype "passive"))
    )
    (net (code "18") (name "/ESP_USB_P") (class "Default")
      (node (ref "R24") (pin "2") (pinfunction "2_2") (pintype "passive"))
      (node (ref "R26") (pin "2") (pinfunction "2_2") (pintype "passive"))
      (node (ref "U1") (pin "24") (pinfunction "USB_D+/GPIO20/RTC_GPIO20/U1CTS/ADC2_CH9/CLK_OUT1_24") (pintype "passive"))
    )
    (net (code "19") (name "/FTDI_RESET") (class "Default")
      (node (ref "C7") (pin "2") (pinfunction "2_2") (pintype "passive"))
      (node (ref "R8") (pin "2") (pinfunction "2_2") (pintype "passive"))
      (node (ref "U2") (pin "11") (pinfunction "~{RESET}_11") (pintype "passive"))
    )
    (net (code "20") (name "/FTDI_USB_N") (class "Default")
      (node (ref "R6") (pin "2") (pinfunction "2_2") (pintype "passive"))
      (node (ref "U2") (pin "9") (pinfunction "USBDM_9") (pintype "passive"))
    )
    (net (code "21") (name "/FTDI_USB_P") (class "Default")
      (node (ref "R7") (pin "2") (pinfunction "2_2") (pintype "passive"))
      (node (ref "U2") (pin "8") (pinfunction "USBDP_8") (pintype "passive"))
    )
    (net (code "22") (name "/GPIO0") (class "Default")
      (node (ref "R21") (pin "2") (pinfunction "2_2") (pintype "passive"))
      (node (ref "R22") (pin "2") (pinfunction "2_2") (pintype "passive"))
      (node (ref "U1") (pin "4") (pinfunction "GPIO0/RTC_GPIO0_4") (pintype "passive"))
    )
    (net (code "23") (name "/GPIO1") (class "Default")
      (node (ref "J1") (pin "4") (pinfunction "4_4") (pintype "passive"))
      (node (ref "U1") (pin "5") (pinfunction "GPIO1/RTC_GPIO1/TOUCH1/ADC1_CH0_5") (pintype "passive"))
    )
    (net (code "24") (name "/GPIO2") (class "Default")
      (node (ref "D2") (pin "1") (pinfunction "Cathode_1") (pintype "passive"))
      (node (ref "J1") (pin "5") (pinfunction "5_5") (pintype "passive"))
      (node (ref "U1") (pin "6") (pinfunction "GPIO2/RTC_GPIO2/TOUCH2/ADC1_CH1_6") (pintype "passive"))
    )
    (net (code "25") (name "/GPIO3") (class "Default")
      (node (ref "J1") (pin "6") (pinfunction "6_6") (pintype "passive"))
      (node (ref "U1") (pin "7") (pinfunction "GPIO3/RTC_GPIO3/TOUCH3/ADC1_CH2_7") (pintype "passive"))
    )
    (net (code "26") (name "/GPIO4") (class "Default")
      (node (ref "J1") (pin "7") (pinfunction "7_7") (pintype "passive"))
      (node (ref "U1") (pin "8") (pinfunction "GPIO4/RTC_GPIO4/TOUCH4/ADC1_CH3_8") (pintype "passive"))
    )
    (net (code "27") (name "/GPIO5") (class "Default")
      (node (ref "J1") (pin "8") (pinfunction "8_8") (pintype "passive"))
      (node (ref "U1") (pin "9") (pinfunction "GPIO5/RTC_GPIO5/TOUCH5/ADC1_CH4_9") (pintype "passive"))
    )
    (net (code "28") (name "/GPIO6") (class "Default")
      (node (ref "J1") (pin "9") (pinfunction "9_9") (pintype "passive"))
      (node (ref "U1") (pin "10") (pinfunction "GPIO6/RTC_GPIO6/TOUCH6/ADC1_CH5_10") (pintype "passive"))
    )
    (net (code "29") (name "/GPIO7") (class "Default")
      (node (ref "J1") (pin "10") (pinfunction "10_10") (pintype "passive"))
      (node (ref "U1") (pin "11") (pinfunction "GPIO7/RTC_GPIO7/TOUCH7/ADC1_CH6_11") (pintype "passive"))
    )
    (net (code "30") (name "/GPIO8") (class "Default")
      (node (ref "J1") (pin "11") (pinfunction "11_11") (pintype "passive"))
      (node (ref "U1") (pin "12") (pinfunction "GPIO8/RTC_GPIO8/TOUCH8/ADC1_CH7/SUBSPICS1_12") (pintype "passive"))
    )
    (net (code "31") (name "/GPIO9") (class "Default")
      (node (ref "J1") (pin "12") (pinfunction "12_12") (pintype "passive"))
      (node (ref "U1") (pin "13") (pinfunction "GPIO9/RTC_GPIO9/TOUCH9/ADC1_CH8/FSPIHD/SUBSPIHD_13") (pintype "passive"))
    )
    (net (code "32") (name "/GPIO10") (class "Default")
      (node (ref "J1") (pin "13") (pinfunction "13_13") (pintype "passive"))
      (node (ref "U1") (pin "14") (pinfunction "GPIO10/RTC_GPIO10/TOUCH10/ADC1_CH9/FSPICS0/FSPIIO4/SUBSPICS0_14") (pintype "passive"))
    )
    (net (code "33") (name "/GPIO11") (class "Default")
      (node (ref "J1") (pin "14") (pinfunction "14_14") (pintype "passive"))
      (node (ref "U1") (pin "15") (pinfunction "GPIO11/RTC_GPIO11/TOUCH11/ADC2_CH0/FSPID/FSPIIO5/SUBSPID_15") (pintype "passive"))
    )
    (net (code "34") (name "/GPIO12") (class "Default")
      (node (ref "J1") (pin "15") (pinfunction "15_15") (pintype "passive"))
      (node (ref "U1") (pin "16") (pinfunction "GPIO12/RTC_GPIO12/TOUCH12/ADC2_CH1/FSPICLK/FSPIIO6/SUBSPICLK_16") (pintype "passive"))
    )
    (net (code "35") (name "/GPIO13") (class "Default")
      (node (ref "J1") (pin "16") (pinfunction "16_16") (pintype "passive"))
      (node (ref "U1") (pin "17") (pinfunction "GPIO13/RTC_GPIO13/TOUCH13/ADC2_CH2/FSPIQ/FSPIIO7/SUBSPIQ_17") (pintype "passive"))
    )
    (net (code "36") (name "/GPIO14") (class "Default")
      (node (ref "J1") (pin "17") (pinfunction "17_17") (pintype "passive"))
      (node (ref "U1") (pin "18") (pinfunction "GPIO14/RTC_GPIO14/TOUCH14/ADC2_CH3/FSPIWP/FSPIDQS/SUBSPIWP_18") (pintype "passive"))
    )
    (net (code "37") (name "/GPIO15") (class "Default")
      (node (ref "J1") (pin "18") (pinfunction "18_18") (pintype "passive"))
      (node (ref "U1") (pin "19") (pinfunction "GPIO15/RTC_GPIO15/U0RTS/ADC2_CH4/XTAL_32K_P_19") (pintype "passive"))
    )
    (net (code "38") (name "/GPIO16") (class "Default")
      (node (ref "J1") (pin "19") (pinfunction "19_19") (pintype "passive"))
      (node (ref "U1") (pin "20") (pinfunction "GPIO16/RTC_GPIO16/U0CTS/ADC2_CH5/XTAL_32K_N_20") (pintype "passive"))
    )
    (net (code "39") (name "/GPIO17") (class "Default")
      (node (ref "J1") (pin "20") (pinfunction "20_20") (pintype "passive"))
      (node (ref "U1") (pin "21") (pinfunction "GPIO17/RTC_GPIO17/U1TXD/ADC2_CH6_21") (pintype "passive"))
    )
    (net (code "40") (name "/GPIO18") (class "Default")
      (node (ref "J1") (pin "21") (pinfunction "21_21") (pintype "passive"))
      (node (ref "U1") (pin "22") (pinfunction "GPIO18/RTC_GPIO18/U1RXD/ADC2_CH7/CLK_OUT3_22") (pintype "passive"))
    )
    (net (code "41") (name "/GPIO21") (class "Default")
      (node (ref "J2") (pin "19") (pinfunction "19_19") (pintype "passive"))
      (node (ref "U1") (pin "25") (pinfunction "GPIO21/RTC_GPIO21_25") (pintype "passive"))
    )
    (net (code "42") (name "/GPIO26") (class "Default")
      (node (ref "J2") (pin "18") (pinfunction "18_18") (pintype "passive"))
      (node (ref "U1") (pin "26") (pinfunction "GPIO26/SPICS1_26") (pintype "passive"))
    )
    (net (code "43") (name "/GPIO33") (class "Default")
      (node (ref "J2") (pin "17") (pinfunction "17_17") (pintype "passive"))
      (node (ref "U1") (pin "28") (pinfunction "GPIO33/SPIIO4/FSPIHD/SUBSPIHD_28") (pintype "passive"))
    )
    (net (code "44") (name "/GPIO34") (class "Default")
      (node (ref "J2") (pin "16") (pinfunction "16_16") (pintype "passive"))
      (node (ref "U1") (pin "29") (pinfunction "GPIO34/SPIIO5/FSPICS0/SUBSPICS0_29") (pintype "passive"))
    )
    (net (code "45") (name "/GPIO35") (class "Default")
      (node (ref "J2") (pin "15") (pinfunction "15_15") (pintype "passive"))
      (node (ref "U1") (pin "31") (pinfunction "GPIO35/SPIIO6/FSPID/SUBSPID_31") (pintype "passive"))
    )
    (net (code "46") (name "/GPIO36") (class "Default")
      (node (ref "J2") (pin "14") (pinfunction "14_14") (pintype "passive"))
      (node (ref "U1") (pin "32") (pinfunction "GPIO36/SPIIO7/FSPICLK/SUBSPICLK_32") (pintype "passive"))
    )
    (net (code "47") (name "/GPIO37") (class "Default")
      (node (ref "J2") (pin "13") (pinfunction "13_13") (pintype "passive"))
      (node (ref "U1") (pin "33") (pinfunction "GPIO37/SPIDQS/FSPIQ/SUBSPIQ_33") (pintype "passive"))
    )
    (net (code "48") (name "/GPIO38") (class "Default")
      (node (ref "J2") (pin "12") (pinfunction "12_12") (pintype "passive"))
      (node (ref "U1") (pin "34") (pinfunction "FSPIWP/GPIO38/SUBSPIWP_34") (pintype "passive"))
    )
    (net (code "49") (name "/GPIO39") (class "Default")
      (node (ref "J2") (pin "11") (pinfunction "11_11") (pintype "passive"))
      (node (ref "U1") (pin "35") (pinfunction "GPIO39/MTCK/CLK_OUT3/SUBSPICS1_35") (pintype "passive"))
    )
    (net (code "50") (name "/GPIO40") (class "Default")
      (node (ref "J2") (pin "10") (pinfunction "10_10") (pintype "passive"))
      (node (ref "U1") (pin "36") (pinfunction "GPIO40/MTDO/CLK_OUT2_36") (pintype "passive"))
    )
    (net (code "51") (name "/GPIO41") (class "Default")
      (node (ref "J2") (pin "9") (pinfunction "9_9") (pintype "passive"))
      (node (ref "U1") (pin "37") (pinfunction "GPIO41/MTDI/CLK_OUT1_37") (pintype "passive"))
    )
    (net (code "52") (name "/GPIO42") (class "Default")
      (node (ref "J2") (pin "8") (pinfunction "8_8") (pintype "passive"))
      (node (ref "U1") (pin "38") (pinfunction "GPIO42/MTMS_38") (pintype "passive"))
    )
    (net (code "53") (name "/GPIO45") (class "Default")
      (node (ref "J2") (pin "5") (pinfunction "5_5") (pintype "passive"))
      (node (ref "U1") (pin "41") (pinfunction "GPIO45_41") (pintype "passive"))
    )
    (net (code "54") (name "/GPIO46") (class "Default")
      (node (ref "J2") (pin "4") (pinfunction "4_4") (pintype "passive"))
      (node (ref "U1") (pin "44") (pinfunction "GPIO46_44") (pintype "passive"))
    )
    (net (code "55") (name "/GPIO47") (class "Default")
      (node (ref "J2") (pin "23") (pinfunction "23_23") (pintype "passive"))
      (node (ref "U1") (pin "27") (pinfunction "GPIO47/SPICLK_P_DIFF/SUBSPICLK_P_DIFF_27") (pintype "passive"))
    )
    (net (code "56") (name "/GPIO48") (class "Default")
      (node (ref "J2") (pin "22") (pinfunction "22_22") (pintype "passive"))
      (node (ref "U1") (pin "30") (pinfunction "GPIO48/SPICLK_N_DIFF/SUBSPICLK_N_DIFF_30") (pintype "passive"))
    )
    (net (code "57") (name "/RTS_FTDI") (class "Default")
      (node (ref "Q1") (pin "2") (pinfunction "E_2") (pintype "passive"))
      (node (ref "R18") (pin "10") (pinfunction "5_10") (pintype "passive"))
      (node (ref "U2") (pin "19") (pinfunction "~{RTS}_19") (pintype "passive"))
    )
    (net (code "58") (name "/RXD_FTDI") (class "Default")
      (node (ref "R19") (pin "2") (pinfunction "2_2") (pintype "passive"))
      (node (ref "U2") (pin "1") (pinfunction "RXD_1") (pintype "passive"))
    )
    (net (code "59") (name "/TXD_FTDI") (class "Default")
      (node (ref "R20") (pin "2") (pinfunction "2_2") (pintype "passive"))
      (node (ref "U2") (pin "17") (pinfunction "TXD_17") (pintype "passive"))
    )
    (net (code "60") (name "/U0RXD") (class "Default")
      (node (ref "J2") (pin "6") (pinfunction "6_6") (pintype "passive"))
      (node (ref "R19") (pin "1") (pinfunction "1_1") (pintype "passive"))
      (node (ref "U1") (pin "40") (pinfunction "U0RXD/GPIO44/CLK_OUT2_40") (pintype "passive"))
    )
    (net (code "61") (name "/U0TXD") (class "Default")
      (node (ref "J2") (pin "7") (pinfunction "7_7") (pintype "passive"))
      (node (ref "R20") (pin "1") (pinfunction "1_1") (pintype "passive"))
      (node (ref "U1") (pin "39") (pinfunction "U0TXD/GPIO43/CLK_OUT1_39") (pintype "passive"))
    )
    (net (code "62") (name "/VBUS_SENSE") (class "Default")
      (node (ref "R10") (pin "1") (pinfunction "1_1") (pintype "passive"))
      (node (ref "R13") (pin "11") (pinfunction "6_11") (pintype "passive"))
      (node (ref "U2") (pin "16") (pinfunction "CBUS3_16") (pintype "passive"))
    )
    (net (code "63") (name "GND") (class "Default")
      (node (ref "C1") (pin "1") (pinfunction "1_1") (pintype "passive"))
      (node (ref "C10") (pin "1") (pinfunction "1_1") (pintype "passive"))
      (node (ref "C11") (pin "1") (pinfunction "1_1") (pintype "passive"))
      (node (ref "C12") (pin "1") (pinfunction "1_1") (pintype "passive"))
      (node (ref "C13") (pin "1") (pinfunction "1_1") (pintype "passive"))
      (node (ref "C14") (pin "1") (pinfunction "1_1") (pintype "passive"))
      (node (ref "C15") (pin "1") (pinfunction "1_1") (pintype "passive"))
      (node (ref "C16") (pin "1") (pinfunction "1_1") (pintype "passive"))
      (node (ref "C17") (pin "1") (pinfunction "1_1") (pintype "passive"))
      (node (ref "C2") (pin "1") (pinfunction "1_1") (pintype "passive"))
      (node (ref "C3") (pin "1") (pinfunction "1_1") (pintype "passive"))
      (node (ref "C4") (pin "1") (pinfunction "1_1") (pintype "passive"))
      (node (ref "C5") (pin "1") (pinfunction "1_1") (pintype "passive"))
      (node (ref "C6") (pin "1") (pinfunction "1_1") (pintype "passive"))
      (node (ref "C7") (pin "1") (pinfunction "1_1") (pintype "passive"))
      (node (ref "C8") (pin "1") (pinfunction "1_1") (pintype "passive"))
      (node (ref "C9") (pin "1") (pinfunction "1_1") (pintype "passive"))
      (node (ref "D1") (pin "1") (pinfunction "Cathode_1") (pintype "passive"))
      (node (ref "D3") (pin "1") (pinfunction "1_1") (pintype "passive"))
      (node (ref "D4") (pin "1") (pinfunction "1_1") (pintype "passive"))
      (node (ref "D5") (pin "1") (pinfunction "1_1") (pintype "passive"))
      (node (ref "D6") (pin "1") (pinfunction "1_1") (pintype "passive"))
      (node (ref "D7") (pin "1") (pinfunction "1_1") (pintype "passive"))
      (node (ref "D8") (pin "1") (pinfunction "1_1") (pintype "passive"))
      (node (ref "J1") (pin "1") (pinfunction "1_1") (pintype "passive"))
      (node (ref "J1") (pin "23") (pinfunction "23_23") (pintype "passive"))
      (node (ref "J2") (pin "2") (pinfunction "2_2") (pintype "passive"))
      (node (ref "J2") (pin "24") (pinfunction "24_24") (pintype "passive"))
      (node (ref "J3") (pin "A1B12") (pinfunction "GND_A1B12_A1B12") (pintype "passive"))
      (node (ref "J3") (pin "B1A12") (pinfunction "GND_B1A12_B1A12") (pintype "passive"))
      (node (ref "J3") (pin "S1") (pinfunction "SHIELD_1_S1") (pintype "passive"))
      (node (ref "J3") (pin "S2") (pinfunction "SHIELD_2_S2") (pintype "passive"))
      (node (ref "J3") (pin "S3") (pinfunction "SHIELD_3_S3") (pintype "passive"))
      (node (ref "J3") (pin "S4") (pinfunction "SHIELD_4_S4") (pintype "passive"))
      (node (ref "J4") (pin "A1B12") (pinfunction "GND_A1B12_A1B12") (pintype "passive"))
      (node (ref "J4") (pin "B1A12") (pinfunction "GND_B1A12_B1A12") (pintype "passive"))
      (node (ref "J4") (pin "S1") (pinfunction "SHIELD_1_S1") (pintype "passive"))
      (node (ref "J4") (pin "S2") (pinfunction "SHIELD_2_S2") (pintype "passive"))
      (node (ref "J4") (pin "S3") (pinfunction "SHIELD_3_S3") (pintype "passive"))
      (node (ref "J4") (pin "S4") (pinfunction "SHIELD_4_S4") (pintype "passive"))
      (node (ref "R11") (pin "1") (pinfunction "1_1") (pintype "passive"))
      (node (ref "R12") (pin "1") (pinfunction "1_1") (pintype "passive"))
      (node (ref "R13") (pin "10") (pinfunction "5_10") (pintype "passive"))
      (node (ref "R14") (pin "1") (pinfunction "1_1") (pintype "passive"))
      (node (ref "R15") (pin "1") (pinfunction "1_1") (pintype "passive"))
      (node (ref "R9") (pin "11") (pinfunction "6_11") (pintype "passive"))
      (node (ref "SW1") (pin "3") (pinfunction "3_3") (pintype "passive"))
      (node (ref "SW1") (pin "4") (pinfunction "4_4") (pintype "passive"))
      (node (ref "SW2") (pin "3") (pinfunction "3_3") (pintype "passive"))
      (node (ref "SW2") (pin "4") (pinfunction "4_4") (pintype "passive"))
      (node (ref "U1") (pin "1") (pinfunction "GND_01_1") (pintype "power_in"))
      (node (ref "U1") (pin "2") (pinfunction "GND_02_2") (pintype "power_in"))
      (node (ref "U1") (pin "42") (pinfunction "GND_42") (pintype "power_in"))
      (node (ref "U1") (pin "43") (pinfunction "GND_43") (pintype "power_in"))
      (node (ref "U1") (pin "46") (pinfunction "GND_46_46") (pintype "power_in"))
      (node (ref "U1") (pin "47") (pinfunction "GND_47_47") (pintype "power_in"))
      (node (ref "U1") (pin "48") (pinfunction "GND_48_48") (pintype "power_in"))
      (node (ref "U1") (pin "49") (pinfunction "GND_49_49") (pintype "power_in"))
      (node (ref "U1") (pin "50") (pinfunction "GND_50_50") (pintype "power_in"))
      (node (ref "U1") (pin "51") (pinfunction "GND_51_51") (pintype "power_in"))
      (node (ref "U1") (pin "52") (pinfunction "GND_52_52") (pintype "power_in"))
      (node (ref "U1") (pin "53") (pinfunction "GND_53_53") (pintype "power_in"))
      (node (ref "U1") (pin "54") (pinfunction "GND_54_54") (pintype "power_in"))
      (node (ref "U1") (pin "55") (pinfunction "GND_55_55") (pintype "power_in"))
      (node (ref "U1") (pin "56") (pinfunction "GND_56_56") (pintype "power_in"))
      (node (ref "U1") (pin "57") (pinfunction "GND_57_57") (pintype "power_in"))
      (node (ref "U1") (pin "58") (pinfunction "GND_58_58") (pintype "power_in"))
      (node (ref "U1") (pin "59") (pinfunction "GND_59_59") (pintype "power_in"))
      (node (ref "U1") (pin "60") (pinfunction "GND_60_60") (pintype "power_in"))
      (node (ref "U1") (pin "61") (pinfunction "GND_61_61") (pintype "power_in"))
      (node (ref "U1") (pin "62") (pinfunction "GND_62_62") (pintype "power_in"))
      (node (ref "U1") (pin "63") (pinfunction "GND_63_63") (pintype "power_in"))
      (node (ref "U1") (pin "64") (pinfunction "GND_64_64") (pintype "power_in"))
      (node (ref "U1") (pin "65") (pinfunction "GND_65_65") (pintype "power_in"))
      (node (ref "U1") (pin "66") (pinfunction "GND_66_66") (pintype "power_in"))
      (node (ref "U1") (pin "67") (pinfunction "GND_67_67") (pintype "power_in"))
      (node (ref "U1") (pin "68") (pinfunction "GND_68_68") (pintype "power_in"))
      (node (ref "U1") (pin "69") (pinfunction "GND_69_69") (pintype "power_in"))
      (node (ref "U1") (pin "70") (pinfunction "GND_70_70") (pintype "power_in"))
      (node (ref "U1") (pin "71") (pinfunction "GND_71_71") (pintype "power_in"))
      (node (ref "U1") (pin "72") (pinfunction "GND_72_72") (pintype "power_in"))
      (node (ref "U1") (pin "73") (pinfunction "GND_73_73") (pintype "power_in"))
      (node (ref "U2") (pin "13") (pinfunction "GND_13") (pintype "power_in"))
      (node (ref "U2") (pin "21") (pinfunction "GND_21") (pintype "power_in"))
      (node (ref "U2") (pin "3") (pinfunction "GND_3") (pintype "power_in"))
      (node (ref "U3") (pin "2") (pinfunction "GND_2") (pintype "power_in"))
      (node (ref "U3") (pin "4") (pinfunction "GND_4") (pintype "power_in"))
    )
    (net (code "64") (name "Net-(D1-Anode)") (class "Default")
      (node (ref "D1") (pin "2") (pinfunction "Anode_2") (pintype "passive"))
      (node (ref "R3") (pin "10") (pinfunction "5_10") (pintype "passive"))
    )
    (net (code "65") (name "Net-(D2-Anode)") (class "Default")
      (node (ref "D2") (pin "2") (pinfunction "Anode_2") (pintype "passive"))
      (node (ref "R4") (pin "10") (pinfunction "5_10") (pintype "passive"))
    )
    (net (code "66") (name "Net-(J3-CC1)") (class "Default")
      (node (ref "J3") (pin "A5") (pinfunction "CC1_A5") (pintype "passive"))
      (node (ref "R12") (pin "2") (pinfunction "2_2") (pintype "passive"))
    )
    (net (code "67") (name "Net-(J3-CC2)") (class "Default")
      (node (ref "J3") (pin "B5") (pinfunction "CC2_B5") (pintype "passive"))
      (node (ref "R11") (pin "2") (pinfunction "2_2") (pintype "passive"))
    )
    (net (code "68") (name "Net-(J4-CC1)") (class "Default")
      (node (ref "J4") (pin "A5") (pinfunction "CC1_A5") (pintype "passive"))
      (node (ref "R15") (pin "2") (pinfunction "2_2") (pintype "passive"))
    )
    (net (code "69") (name "Net-(J4-CC2)") (class "Default")
      (node (ref "J4") (pin "B5") (pinfunction "CC2_B5") (pintype "passive"))
      (node (ref "R14") (pin "2") (pinfunction "2_2") (pintype "passive"))
    )
    (net (code "70") (name "Net-(Q1-B)") (class "Default")
      (node (ref "Q1") (pin "1") (pinfunction "B_1") (pintype "passive"))
      (node (ref "R16") (pin "11") (pinfunction "6_11") (pintype "passive"))
    )
    (net (code "71") (name "Net-(Q2-B)") (class "Default")
      (node (ref "Q2") (pin "1") (pinfunction "B_1") (pintype "passive"))
      (node (ref "R18") (pin "11") (pinfunction "6_11") (pintype "passive"))
    )
    (net (code "72") (name "Net-(R9-5)") (class "Default")
      (node (ref "R9") (pin "10") (pinfunction "5_10") (pintype "passive"))
      (node (ref "U2") (pin "15") (pinfunction "CBUS0_15") (pintype "passive"))
    )
    (net (code "73") (name "Net-(U2-VCC)") (class "Default")
      (node (ref "C2") (pin "2") (pinfunction "2_2") (pintype "passive"))
      (node (ref "C3") (pin "2") (pinfunction "2_2") (pintype "passive"))
      (node (ref "R1") (pin "2") (pinfunction "2_2") (pintype "passive"))
      (node (ref "R2") (pin "2") (pinfunction "2_2") (pintype "passive"))
      (node (ref "U2") (pin "12") (pinfunction "VCC_12") (pintype "power_in"))
    )
    (net (code "74") (name "unconnected-(J1-Pad24)") (class "Default")
      (node (ref "J1") (pin "24") (pinfunction "24_24") (pintype "passive+no_connect"))
    )
    (net (code "75") (name "unconnected-(J3-SBU1-PadA8)") (class "Default")
      (node (ref "J3") (pin "A8") (pinfunction "SBU1_A8") (pintype "passive"))
    )
    (net (code "76") (name "unconnected-(J3-SBU2-PadB8)") (class "Default")
      (node (ref "J3") (pin "B8") (pinfunction "SBU2_B8") (pintype "passive"))
    )
    (net (code "77") (name "unconnected-(J4-SBU1-PadA8)") (class "Default")
      (node (ref "J4") (pin "A8") (pinfunction "SBU1_A8") (pintype "passive"))
    )
    (net (code "78") (name "unconnected-(J4-SBU2-PadB8)") (class "Default")
      (node (ref "J4") (pin "B8") (pinfunction "SBU2_B8") (pintype "passive"))
    )
    (net (code "79") (name "unconnected-(U2-CBUS1-Pad14)") (class "Default")
      (node (ref "U2") (pin "14") (pinfunction "CBUS1_14") (pintype "passive+no_connect"))
    )
    (net (code "80") (name "unconnected-(U2-CBUS2-Pad7)") (class "Default")
      (node (ref "U2") (pin "7") (pinfunction "CBUS2_7") (pintype "passive+no_connect"))
    )
    (net (code "81") (name "unconnected-(U2-~{CTS}-Pad6)") (class "Default")
      (node (ref "U2") (pin "6") (pinfunction "~{CTS}_6") (pintype "passive"))
    )
    (net (code "82") (name "unconnected-(U2-~{DCD}-Pad5)") (class "Default")
      (node (ref "U2") (pin "5") (pinfunction "~{DCD}_5") (pintype "passive+no_connect"))
    )
    (net (code "83") (name "unconnected-(U2-~{DSR}-Pad4)") (class "Default")
      (node (ref "U2") (pin "4") (pinfunction "~{DSR}_4") (pintype "passive+no_connect"))
    )
    (net (code "84") (name "unconnected-(U2-~{RI}-Pad2)") (class "Default")
      (node (ref "U2") (pin "2") (pinfunction "~{RI}_2") (pintype "passive+no_connect"))
    )
  )
)
